# ic.net
KiCad netlist of a schematic drawn in Altium Designer
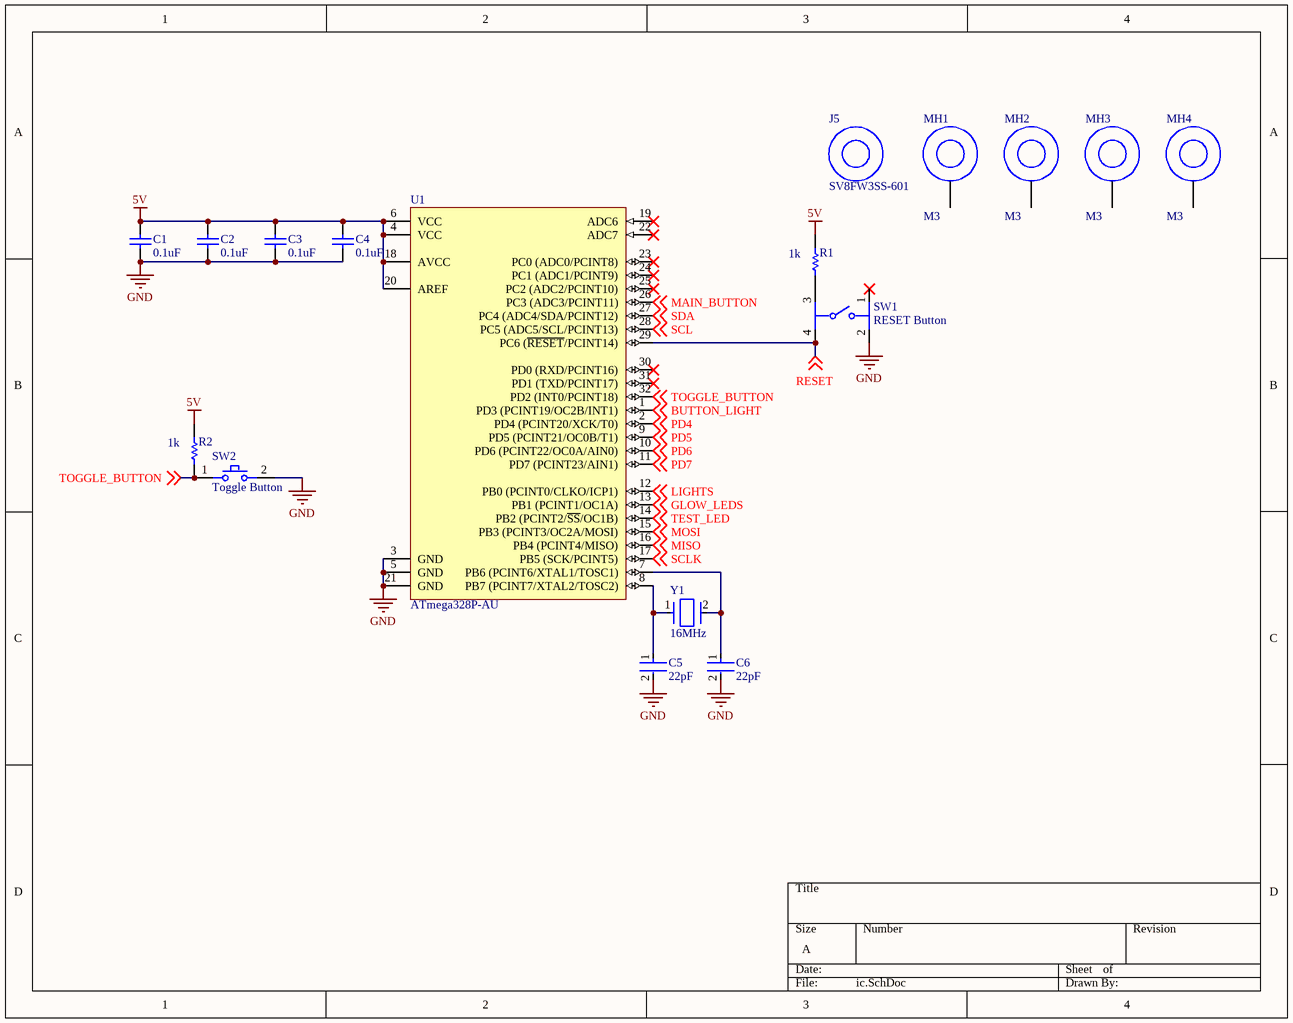
[diagram p0: ic.SchDoc]

(export (version "E")
  (design (tool "Eeschema 10.0.6"))
  (components
    (comp (ref "C1")
      (value "0.1uF")
      (footprint "CAPC2013X135X45ML10T25")
      (description "Chip Capacitor, 0.1 uF, +/- 10%, 50 V, -55 to 125 degC, 0805 (2012 Metric), RoHS, Tape and Reel")
      (fields (field (name "VOLTAGE") "50V") (field (name "TOLERANCE") "10%"))
      (libsource (lib "Altium Content Vault") (part "CAP-NP-2"))
    )
    (comp (ref "C2")
      (value "0.1uF")
      (footprint "CAPC2013X135X45ML10T25")
      (description "Chip Capacitor, 0.1 uF, +/- 10%, 50 V, -55 to 125 degC, 0805 (2012 Metric), RoHS, Tape and Reel")
      (fields (field (name "VOLTAGE") "50V") (field (name "TOLERANCE") "10%"))
      (libsource (lib "Altium Content Vault") (part "CAP-NP-2"))
    )
    (comp (ref "C3")
      (value "0.1uF")
      (footprint "CAPC2013X135X45ML10T25")
      (description "Chip Capacitor, 0.1 uF, +/- 10%, 50 V, -55 to 125 degC, 0805 (2012 Metric), RoHS, Tape and Reel")
      (fields (field (name "VOLTAGE") "50V") (field (name "TOLERANCE") "10%"))
      (libsource (lib "Altium Content Vault") (part "CAP-NP-2"))
    )
    (comp (ref "C4")
      (value "0.1uF")
      (footprint "CAPC2013X135X45ML10T25")
      (description "Chip Capacitor, 0.1 uF, +/- 10%, 50 V, -55 to 125 degC, 0805 (2012 Metric), RoHS, Tape and Reel")
      (fields (field (name "VOLTAGE") "50V") (field (name "TOLERANCE") "10%"))
      (libsource (lib "Altium Content Vault") (part "CAP-NP-2"))
    )
    (comp (ref "C5")
      (value "22pF")
      (footprint "FP-C0805C-DN-MFG")
      (description "CAP CER 22PF 100V 5% NP0 0805")
      (fields
        (field (name "OCTOPART") "https://octopart.com/c0805c220j1gactu-kemet-3791395")
        (field (name "TOLERANCE") "0.05")
      )
      (libsource (lib "Altium Content Vault") (part "b4654b650e69147ec39a6b967a45e02"))
    )
    (comp (ref "C6")
      (value "22pF")
      (footprint "FP-C0805C-DN-MFG")
      (description "CAP CER 22PF 100V 5% NP0 0805")
      (fields
        (field (name "OCTOPART") "https://octopart.com/c0805c220j1gactu-kemet-3791395")
        (field (name "TOLERANCE") "0.05")
      )
      (libsource (lib "Altium Content Vault") (part "b4654b650e69147ec39a6b967a45e02"))
    )
    (comp (ref "J5")
      (value "SV8FW3SS-601")
      (footprint "SV8FW3SS-601")
      (libsource (lib "Fairy Light Sch Lib") (part "SV8FW3SS-601"))
    )
    (comp (ref "MH1")
      (value "M3")
      (footprint "PTH_M3")
      (description "M3 Plated Through Hole")
      (libsource (lib "Schlib1") (part "PTH"))
    )
    (comp (ref "MH2")
      (value "M3")
      (footprint "PTH_M3")
      (description "M3 Plated Through Hole")
      (libsource (lib "Schlib1") (part "PTH"))
    )
    (comp (ref "MH3")
      (value "M3")
      (footprint "PTH_M3")
      (description "M3 Plated Through Hole")
      (libsource (lib "Schlib1") (part "PTH"))
    )
    (comp (ref "MH4")
      (value "M3")
      (footprint "PTH_M3")
      (description "M3 Plated Through Hole")
      (libsource (lib "Schlib1") (part "PTH"))
    )
    (comp (ref "R1")
      (value "1k")
      (footprint "RESC2013X50X30NL20T20")
      (fields (field (name "PART NUMBER") "CRCW08051K00FKEA") (field (name "MANUFACTURER") "Vishay Dale"))
      (libsource (lib "Altium Content Vault") (part "RES"))
    )
    (comp (ref "R2")
      (value "1k")
      (footprint "RESC2013X50X30NL20T20")
      (fields (field (name "PART NUMBER") "CRCW08051K00FKEA") (field (name "MANUFACTURER") "Vishay Dale"))
      (libsource (lib "Altium Content Vault") (part "RES"))
    )
    (comp (ref "SW1")
      (value "RESET Button")
      (footprint "FP-PTS645SM43SMTR92LFS-MFG")
      (description "SWITCH TACTILE SPST-NO 0.05A 12V")
      (fields (field (name "MPN") "PTS645SM43SMTR92LFS"))
      (libsource (lib "Altium Content Vault") (part "1adf0dd01260c80cf25a44bfd6b99ba"))
    )
    (comp (ref "SW2")
      (value "Toggle Button")
      (footprint "FP-B3AL-1003P-MFG")
      (description "SWITCH TACTILE SPST-NO 0.05A 16V")
      (fields (field (name "MPN") "B3AL-1003P"))
      (libsource (lib "Altium Content Vault") (part "69e8347f6a24c021ef43a914a4df441"))
    )
    (comp (ref "U1")
      (value "ATmega328P-AU")
      (footprint "32A_M")
      (libsource (lib "Altium Content Vault") (part "MC-8B-ATM48-SQ32"))
    )
    (comp (ref "Y1")
      (value "16MHz")
      (footprint "FP-XRCHA-MFG")
      (description "CRYSTAL 16.0000MHZ 8PF SMD")
      (fields (field (name "TOLERANCE") "100ppm") (field (name "MPN") "XRCHA16M000F0A01R0"))
      (libsource (lib "Altium Content Vault") (part "c23a69dc6c9e2f18f2079038eb95dd1"))
    )
  )
  (nets
    (net (code "1") (name "5V") (class "Default")
      (node (ref "C1") (pin "2") (pinfunction "2_2") (pintype "passive"))
      (node (ref "C2") (pin "2") (pinfunction "2_2") (pintype "passive"))
      (node (ref "C3") (pin "2") (pinfunction "2_2") (pintype "passive"))
      (node (ref "C4") (pin "2") (pinfunction "2_2") (pintype "passive"))
      (node (ref "R1") (pin "2") (pinfunction "2_2") (pintype "passive"))
      (node (ref "R2") (pin "2") (pinfunction "2_2") (pintype "passive"))
      (node (ref "U1") (pin "18") (pinfunction "AVCC_18") (pintype "power_in"))
      (node (ref "U1") (pin "20") (pinfunction "AREF_20") (pintype "passive"))
      (node (ref "U1") (pin "4") (pinfunction "VCC_4") (pintype "power_in"))
      (node (ref "U1") (pin "6") (pinfunction "VCC_6") (pintype "power_in"))
    )
    (net (code "2") (name "BUTTON_LIGHT") (class "Default")
      (node (ref "U1") (pin "1") (pinfunction "PD3_(PCINT19/OC2B/INT1)_1") (pintype "bidirectional"))
    )
    (net (code "3") (name "GLOW_LEDS") (class "Default")
      (node (ref "U1") (pin "13") (pinfunction "PB1_(PCINT1/OC1A)_13") (pintype "bidirectional"))
    )
    (net (code "4") (name "GND") (class "Default")
      (node (ref "C1") (pin "1") (pinfunction "1_1") (pintype "passive"))
      (node (ref "C2") (pin "1") (pinfunction "1_1") (pintype "passive"))
      (node (ref "C3") (pin "1") (pinfunction "1_1") (pintype "passive"))
      (node (ref "C4") (pin "1") (pinfunction "1_1") (pintype "passive"))
      (node (ref "C5") (pin "2") (pinfunction "2_2") (pintype "passive"))
      (node (ref "C6") (pin "2") (pinfunction "2_2") (pintype "passive"))
      (node (ref "SW1") (pin "2") (pinfunction "2_2") (pintype "passive"))
      (node (ref "SW2") (pin "2") (pinfunction "2_2") (pintype "passive"))
      (node (ref "U1") (pin "21") (pinfunction "GND_21") (pintype "power_in"))
      (node (ref "U1") (pin "3") (pinfunction "GND_3") (pintype "power_in"))
      (node (ref "U1") (pin "5") (pinfunction "GND_5") (pintype "power_in"))
    )
    (net (code "5") (name "LIGHTS") (class "Default")
      (node (ref "U1") (pin "12") (pinfunction "PB0_(PCINT0/CLKO/ICP1)_12") (pintype "bidirectional"))
    )
    (net (code "6") (name "MAIN_BUTTON") (class "Default")
      (node (ref "U1") (pin "26") (pinfunction "PC3_(ADC3/PCINT11)_26") (pintype "bidirectional"))
    )
    (net (code "7") (name "MISO") (class "Default")
      (node (ref "U1") (pin "16") (pinfunction "PB4_(PCINT4/MISO)_16") (pintype "bidirectional"))
    )
    (net (code "8") (name "MOSI") (class "Default")
      (node (ref "U1") (pin "15") (pinfunction "PB3_(PCINT3/OC2A/MOSI)_15") (pintype "bidirectional"))
    )
    (net (code "9") (name "Net-(R1-Pad1)") (class "Default")
      (node (ref "R1") (pin "1") (pinfunction "1_1") (pintype "passive"))
      (node (ref "SW1") (pin "3") (pinfunction "3_3") (pintype "passive"))
    )
    (net (code "10") (name "Net-(U1-PB6_(PCINT6{slash}XTAL1{slash}TOSC1))") (class "Default")
      (node (ref "C6") (pin "1") (pinfunction "1_1") (pintype "passive"))
      (node (ref "U1") (pin "7") (pinfunction "PB6_(PCINT6/XTAL1/TOSC1)_7") (pintype "bidirectional"))
      (node (ref "Y1") (pin "2") (pinfunction "2_2") (pintype "passive"))
    )
    (net (code "11") (name "Net-(U1-PB7_(PCINT7{slash}XTAL2{slash}TOSC2))") (class "Default")
      (node (ref "C5") (pin "1") (pinfunction "1_1") (pintype "passive"))
      (node (ref "U1") (pin "8") (pinfunction "PB7_(PCINT7/XTAL2/TOSC2)_8") (pintype "bidirectional"))
      (node (ref "Y1") (pin "1") (pinfunction "1_1") (pintype "passive"))
    )
    (net (code "12") (name "PD4") (class "Default")
      (node (ref "U1") (pin "2") (pinfunction "PD4_(PCINT20/XCK/T0)_2") (pintype "bidirectional"))
    )
    (net (code "13") (name "PD5") (class "Default")
      (node (ref "U1") (pin "9") (pinfunction "PD5_(PCINT21/OC0B/T1)_9") (pintype "bidirectional"))
    )
    (net (code "14") (name "PD6") (class "Default")
      (node (ref "U1") (pin "10") (pinfunction "PD6_(PCINT22/OC0A/AIN0)_10") (pintype "bidirectional"))
    )
    (net (code "15") (name "PD7") (class "Default")
      (node (ref "U1") (pin "11") (pinfunction "PD7_(PCINT23/AIN1)_11") (pintype "bidirectional"))
    )
    (net (code "16") (name "RESET") (class "Default")
      (node (ref "SW1") (pin "4") (pinfunction "4_4") (pintype "passive"))
      (node (ref "U1") (pin "29") (pinfunction "PC6_(~{RESET}/PCINT14)_29") (pintype "bidirectional"))
    )
    (net (code "17") (name "SCL") (class "Default")
      (node (ref "U1") (pin "28") (pinfunction "PC5_(ADC5/SCL/PCINT13)_28") (pintype "bidirectional"))
    )
    (net (code "18") (name "SCLK") (class "Default")
      (node (ref "U1") (pin "17") (pinfunction "PB5_(SCK/PCINT5)_17") (pintype "bidirectional"))
    )
    (net (code "19") (name "SDA") (class "Default")
      (node (ref "U1") (pin "27") (pinfunction "PC4_(ADC4/SDA/PCINT12)_27") (pintype "bidirectional"))
    )
    (net (code "20") (name "TEST_LED") (class "Default")
      (node (ref "U1") (pin "14") (pinfunction "PB2_(PCINT2/~{SS}/OC1B)_14") (pintype "bidirectional"))
    )
    (net (code "21") (name "TOGGLE_BUTTON") (class "Default")
      (node (ref "R2") (pin "1") (pinfunction "1_1") (pintype "passive"))
      (node (ref "SW2") (pin "1") (pinfunction "1_1") (pintype "passive"))
      (node (ref "U1") (pin "32") (pinfunction "PD2_(INT0/PCINT18)_32") (pintype "bidirectional"))
    )
    (net (code "22") (name "unconnected-(MH1-Pad1)") (class "Default")
      (node (ref "MH1") (pin "1") (pinfunction "1_1") (pintype "passive"))
    )
    (net (code "23") (name "unconnected-(MH2-Pad1)") (class "Default")
      (node (ref "MH2") (pin "1") (pinfunction "1_1") (pintype "passive"))
    )
    (net (code "24") (name "unconnected-(MH3-Pad1)") (class "Default")
      (node (ref "MH3") (pin "1") (pinfunction "1_1") (pintype "passive"))
    )
    (net (code "25") (name "unconnected-(MH4-Pad1)") (class "Default")
      (node (ref "MH4") (pin "1") (pinfunction "1_1") (pintype "passive"))
    )
    (net (code "26") (name "unconnected-(SW1-Pad1)") (class "Default")
      (node (ref "SW1") (pin "1") (pinfunction "1_1") (pintype "passive+no_connect"))
    )
    (net (code "27") (name "unconnected-(U1-ADC6-Pad19)") (class "Default")
      (node (ref "U1") (pin "19") (pinfunction "ADC6_19") (pintype "input+no_connect"))
    )
    (net (code "28") (name "unconnected-(U1-ADC7-Pad22)") (class "Default")
      (node (ref "U1") (pin "22") (pinfunction "ADC7_22") (pintype "input+no_connect"))
    )
    (net (code "29") (name "unconnected-(U1-PC0_(ADC0{slash}PCINT8)-Pad23)") (class "Default")
      (node (ref "U1") (pin "23") (pinfunction "PC0_(ADC0/PCINT8)_23") (pintype "bidirectional+no_connect"))
    )
    (net (code "30") (name "unconnected-(U1-PC1_(ADC1{slash}PCINT9)-Pad24)") (class "Default")
      (node (ref "U1") (pin "24") (pinfunction "PC1_(ADC1/PCINT9)_24") (pintype "bidirectional+no_connect"))
    )
    (net (code "31") (name "unconnected-(U1-PC2_(ADC2{slash}PCINT10)-Pad25)") (class "Default")
      (node (ref "U1") (pin "25") (pinfunction "PC2_(ADC2/PCINT10)_25") (pintype "bidirectional+no_connect"))
    )
    (net (code "32") (name "unconnected-(U1-PD0_(RXD{slash}PCINT16)-Pad30)") (class "Default")
      (node (ref "U1") (pin "30") (pinfunction "PD0_(RXD/PCINT16)_30") (pintype "bidirectional+no_connect"))
    )
    (net (code "33") (name "unconnected-(U1-PD1_(TXD{slash}PCINT17)-Pad31)") (class "Default")
      (node (ref "U1") (pin "31") (pinfunction "PD1_(TXD/PCINT17)_31") (pintype "bidirectional+no_connect"))
    )
  )
)
